# powersupply.net
KiCad netlist of a schematic drawn in Altium Designer
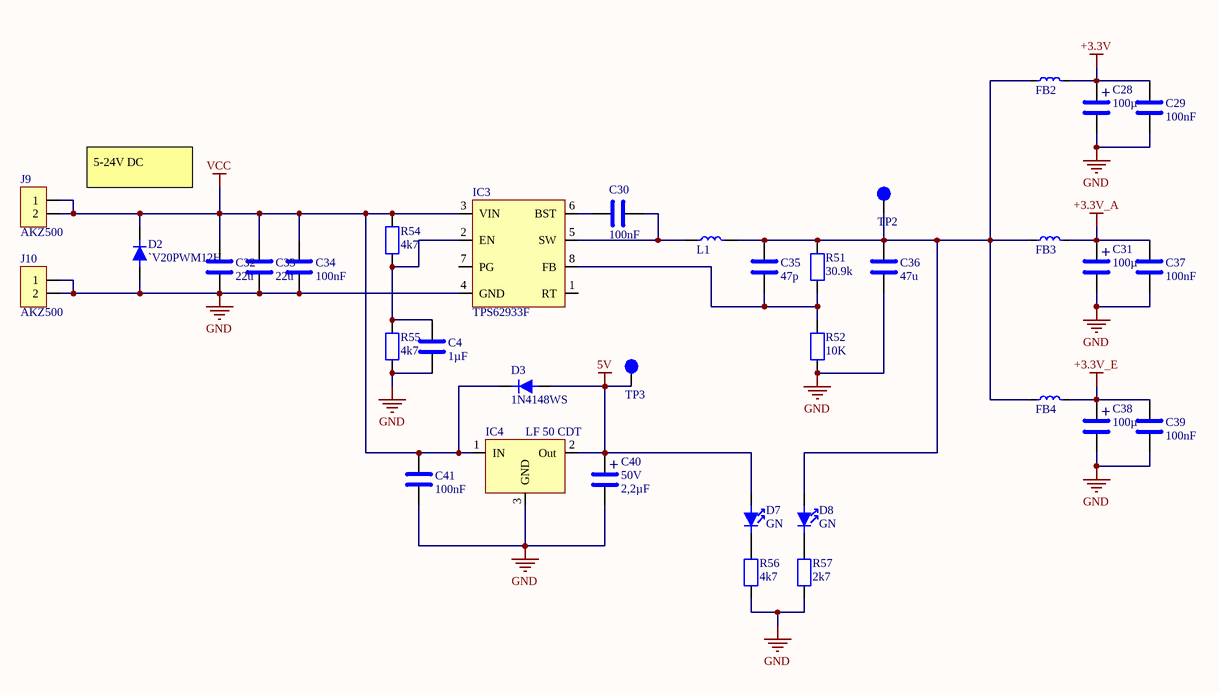
[diagram p0: powersupply.SchDoc]

(export (version "E")
  (design (tool "Eeschema 10.0.6"))
  (components
    (comp (ref "C4")
      (value "1µF")
      (footprint "0805")
      (description "1µF 25V MLCC 0805")
      (fields (field (name "VOLTAGE") "25V"))
      (libsource (lib "capacitor0805") (part "1µF 25V MLCC 0805"))
    )
    (comp (ref "C28")
      (value "100µ")
      (footprint "PANASONIC_C")
      (fields (field (name "VOLTAGE") "16V") (field (name "Comment") "Elko_100uF_16V_PanasonicC"))
      (libsource (lib "elkos") (part "Elko_100uF_16V_PanasonicC"))
    )
    (comp (ref "C29")
      (value "100nF")
      (footprint "0603")
      (description "100nF 50V MLCC 0603")
      (fields (field (name "VOLTAGE") "50V"))
      (libsource (lib "capacitors") (part "100nF 50V MLCC 0603"))
    )
    (comp (ref "C30")
      (value "100nF")
      (footprint "0603")
      (description "100nF 50V MLCC 0603")
      (fields (field (name "VOLTAGE") "50V"))
      (libsource (lib "capacitors") (part "100nF 50V MLCC 0603"))
    )
    (comp (ref "C31")
      (value "100µ")
      (footprint "PANASONIC_C")
      (fields (field (name "VOLTAGE") "16V") (field (name "Comment") "Elko_100uF_16V_PanasonicC"))
      (libsource (lib "elkos") (part "Elko_100uF_16V_PanasonicC"))
    )
    (comp (ref "C32")
      (value "22u")
      (footprint "1210")
      (description "22uF 35V X5R 1210")
      (fields (field (name "VOLTAGE") "35V"))
      (libsource (lib "capacitor1206") (part "22uF 35V X5R 1210"))
    )
    (comp (ref "C33")
      (value "22u")
      (footprint "1210")
      (description "22uF 35V X5R 1210")
      (fields (field (name "VOLTAGE") "35V"))
      (libsource (lib "capacitor1206") (part "22uF 35V X5R 1210"))
    )
    (comp (ref "C34")
      (value "100nF")
      (footprint "0603")
      (description "100nF 50V MLCC 0603")
      (fields (field (name "VOLTAGE") "50V"))
      (libsource (lib "capacitors") (part "100nF 50V MLCC 0603"))
    )
    (comp (ref "C35")
      (value "47p")
      (footprint "0603")
      (description "680pF 50V MLCC 0603")
      (fields (field (name "Comment") "47pF MLCC 0603"))
      (libsource (lib "capacitor0603") (part "47pF MLCC 0603"))
    )
    (comp (ref "C36")
      (value "47u")
      (footprint "1210")
      (description "47uF 16V X7R 1210")
      (fields (field (name "MOUSER PART") "GRM32ER61C476KE15L") (field (name "VOLTAGE") "16V"))
      (libsource (lib "capacitor1206") (part "47uF 16V X7R 1210"))
    )
    (comp (ref "C37")
      (value "100nF")
      (footprint "0603")
      (description "100nF 50V MLCC 0603")
      (fields (field (name "VOLTAGE") "50V"))
      (libsource (lib "capacitors") (part "100nF 50V MLCC 0603"))
    )
    (comp (ref "C38")
      (value "100µ")
      (footprint "PANASONIC_C")
      (fields (field (name "VOLTAGE") "16V") (field (name "Comment") "Elko_100uF_16V_PanasonicC"))
      (libsource (lib "elkos") (part "Elko_100uF_16V_PanasonicC"))
    )
    (comp (ref "C39")
      (value "100nF")
      (footprint "0603")
      (description "100nF 50V MLCC 0603")
      (fields (field (name "VOLTAGE") "50V"))
      (libsource (lib "capacitors") (part "100nF 50V MLCC 0603"))
    )
    (comp (ref "C40")
      (value "2,2µF 50V Size B Elko")
      (footprint "SIZE_B")
      (fields (field (name "VOLTAGE") "50V") (field (name "CAPACITANCE") "2,2µF"))
      (libsource (lib "elkos") (part "2,2µF 50V Size B Elko"))
    )
    (comp (ref "C41")
      (value "100nF")
      (footprint "0603")
      (description "100nF 50V MLCC 0603")
      (fields (field (name "VOLTAGE") "50V"))
      (libsource (lib "capacitors") (part "100nF 50V MLCC 0603"))
    )
    (comp (ref "D2")
      (value "`V20PWM12H")
      (footprint "TO-252AE")
      (description "20A high power diode")
      (libsource (lib "diodes") (part "V20PWM12HM3"))
    )
    (comp (ref "D3")
      (value "1N4148WS")
      (footprint "SOD323")
      (description "Small signal diode")
      (libsource (lib "diodes") (part "1N4148WS"))
    )
    (comp (ref "D7") (value "GN") (footprint "G0805") (libsource (lib "optos") (part "G0805 LED GN")))
    (comp (ref "D8") (value "GN") (footprint "G0805") (libsource (lib "optos") (part "G0805 LED GN")))
    (comp (ref "FB2")
      (value "HI1206N101R-10")
      (footprint "1206")
      (description "3A ferrit bead")
      (libsource (lib "inductors") (part "HI1206N101R-10"))
    )
    (comp (ref "FB3")
      (value "HI1206N101R-10")
      (footprint "1206")
      (description "3A ferrit bead")
      (libsource (lib "inductors") (part "HI1206N101R-10"))
    )
    (comp (ref "FB4")
      (value "HI1206N101R-10")
      (footprint "1206")
      (description "3A ferrit bead")
      (libsource (lib "inductors") (part "HI1206N101R-10"))
    )
    (comp (ref "IC3")
      (value "TPS62933F")
      (footprint "SOT583-8")
      (libsource (lib "regulators") (part "TPS62933F"))
    )
    (comp (ref "IC4")
      (value "LF 50 CDT")
      (footprint "D-PAK")
      (description "5V Spannungsregler D-PAK")
      (libsource (lib "regulators") (part "LF50CDT"))
    )
    (comp (ref "J9")
      (value "AKZ500")
      (footprint "AKZ500/2")
      (libsource (lib "connectors_screw") (part "AKZ500/2"))
    )
    (comp (ref "J10")
      (value "AKZ500")
      (footprint "AKZ500/2")
      (libsource (lib "connectors_screw") (part "AKZ500/2"))
    )
    (comp (ref "L1")
      (value "SRN5040-8R2M")
      (footprint "BOURNS SRN5040")
      (libsource (lib "inductors") (part "SRN5040-8R2M"))
    )
    (comp (ref "R51")
      (value "30.9k")
      (footprint "res0603")
      (description "30k9 100mW 0603")
      (fields (field (name "TOLERANCE") "1%"))
      (libsource (lib "resistors0603") (part "30k9 100mW 0603"))
    )
    (comp (ref "R52")
      (value "10K")
      (footprint "res0603")
      (description "10K 100mW 0603")
      (fields (field (name "TOLERANCE") "1%"))
      (libsource (lib "resistors") (part "10K 100mW 0603"))
    )
    (comp (ref "R54")
      (value "4k7")
      (footprint "res0603")
      (description "4k7 100mW 0603")
      (libsource (lib "resistors") (part "4k7 100mW 0603"))
    )
    (comp (ref "R55")
      (value "4k7")
      (footprint "res0603")
      (description "4k7 100mW 0603")
      (libsource (lib "resistors") (part "4k7 100mW 0603"))
    )
    (comp (ref "R56")
      (value "4k7")
      (footprint "res0603")
      (description "4k7 100mW 0603")
      (libsource (lib "resistors") (part "4k7 100mW 0603"))
    )
    (comp (ref "R57")
      (value "2k7")
      (footprint "res0603")
      (description "2k7 100mW 0603")
      (fields (field (name "TOLERANCE") "1%"))
      (libsource (lib "resistors") (part "2k7 100mW 0603"))
    )
    (comp (ref "TP2") (value "testpoint") (footprint "testpoint") (libsource (lib "misc") (part "testpoint")))
    (comp (ref "TP3") (value "testpoint") (footprint "testpoint") (libsource (lib "misc") (part "testpoint")))
  )
  (nets
    (net (code "1") (name "+3.3V") (class "Default")
      (node (ref "C28") (pin "+") (pinfunction "+_+") (pintype "passive"))
      (node (ref "C29") (pin "1") (pinfunction "1_1") (pintype "passive"))
      (node (ref "FB2") (pin "2") (pinfunction "2_2") (pintype "passive"))
    )
    (net (code "2") (name "+3.3V_A") (class "Default")
      (node (ref "C31") (pin "+") (pinfunction "+_+") (pintype "passive"))
      (node (ref "C37") (pin "1") (pinfunction "1_1") (pintype "passive"))
      (node (ref "FB3") (pin "2") (pinfunction "2_2") (pintype "passive"))
    )
    (net (code "3") (name "+3.3V_E") (class "Default")
      (node (ref "C38") (pin "+") (pinfunction "+_+") (pintype "passive"))
      (node (ref "C39") (pin "1") (pinfunction "1_1") (pintype "passive"))
      (node (ref "FB4") (pin "2") (pinfunction "2_2") (pintype "passive"))
    )
    (net (code "4") (name "5V") (class "Default")
      (node (ref "C40") (pin "1") (pinfunction "1_1") (pintype "passive"))
      (node (ref "D3") (pin "2") (pinfunction "2_2") (pintype "passive"))
      (node (ref "D7") (pin "2") (pinfunction "2_2") (pintype "passive"))
      (node (ref "IC4") (pin "2") (pinfunction "Out_2") (pintype "passive"))
      (node (ref "TP3") (pin "1") (pinfunction "1_1") (pintype "passive"))
    )
    (net (code "5") (name "GND") (class "Default")
      (node (ref "C28") (pin "-") (pinfunction "-_-") (pintype "passive"))
      (node (ref "C29") (pin "2") (pinfunction "2_2") (pintype "passive"))
      (node (ref "C31") (pin "-") (pinfunction "-_-") (pintype "passive"))
      (node (ref "C32") (pin "2") (pinfunction "2_2") (pintype "passive"))
      (node (ref "C33") (pin "2") (pinfunction "2_2") (pintype "passive"))
      (node (ref "C34") (pin "2") (pinfunction "2_2") (pintype "passive"))
      (node (ref "C36") (pin "2") (pinfunction "2_2") (pintype "passive"))
      (node (ref "C37") (pin "2") (pinfunction "2_2") (pintype "passive"))
      (node (ref "C38") (pin "-") (pinfunction "-_-") (pintype "passive"))
      (node (ref "C39") (pin "2") (pinfunction "2_2") (pintype "passive"))
      (node (ref "C4") (pin "2") (pinfunction "2_2") (pintype "passive"))
      (node (ref "C40") (pin "2") (pinfunction "2_2") (pintype "passive"))
      (node (ref "C41") (pin "1") (pinfunction "1_1") (pintype "passive"))
      (node (ref "D2") (pin "2") (pinfunction "2_2") (pintype "passive"))
      (node (ref "IC3") (pin "4") (pinfunction "GND_4") (pintype "passive"))
      (node (ref "IC4") (pin "3") (pinfunction "GND_3") (pintype "passive"))
      (node (ref "J10") (pin "1") (pinfunction "1_1") (pintype "passive"))
      (node (ref "J10") (pin "2") (pinfunction "2_2") (pintype "passive"))
      (node (ref "R52") (pin "1") (pinfunction "1_1") (pintype "passive"))
      (node (ref "R55") (pin "1") (pinfunction "1_1") (pintype "passive"))
      (node (ref "R56") (pin "1") (pinfunction "1_1") (pintype "passive"))
      (node (ref "R57") (pin "1") (pinfunction "1_1") (pintype "passive"))
    )
    (net (code "6") (name "Net-(C35-Pad1)") (class "Default")
      (node (ref "C35") (pin "1") (pinfunction "1_1") (pintype "passive"))
      (node (ref "C36") (pin "1") (pinfunction "1_1") (pintype "passive"))
      (node (ref "D8") (pin "2") (pinfunction "2_2") (pintype "passive"))
      (node (ref "FB2") (pin "1") (pinfunction "1_1") (pintype "passive"))
      (node (ref "FB3") (pin "1") (pinfunction "1_1") (pintype "passive"))
      (node (ref "FB4") (pin "1") (pinfunction "1_1") (pintype "passive"))
      (node (ref "L1") (pin "2") (pinfunction "2_2") (pintype "passive"))
      (node (ref "R51") (pin "2") (pinfunction "2_2") (pintype "passive"))
      (node (ref "TP2") (pin "1") (pinfunction "1_1") (pintype "passive"))
    )
    (net (code "7") (name "Net-(D7-Pad1)") (class "Default")
      (node (ref "D7") (pin "1") (pinfunction "1_1") (pintype "passive"))
      (node (ref "R56") (pin "2") (pinfunction "2_2") (pintype "passive"))
    )
    (net (code "8") (name "Net-(D8-Pad1)") (class "Default")
      (node (ref "D8") (pin "1") (pinfunction "1_1") (pintype "passive"))
      (node (ref "R57") (pin "2") (pinfunction "2_2") (pintype "passive"))
    )
    (net (code "9") (name "Net-(IC3-BST)") (class "Default")
      (node (ref "C30") (pin "1") (pinfunction "1_1") (pintype "passive"))
      (node (ref "IC3") (pin "6") (pinfunction "BST_6") (pintype "passive"))
    )
    (net (code "10") (name "Net-(IC3-EN)") (class "Default")
      (node (ref "C4") (pin "1") (pinfunction "1_1") (pintype "passive"))
      (node (ref "IC3") (pin "2") (pinfunction "EN_2") (pintype "passive"))
      (node (ref "R54") (pin "1") (pinfunction "1_1") (pintype "passive"))
      (node (ref "R55") (pin "2") (pinfunction "2_2") (pintype "passive"))
    )
    (net (code "11") (name "Net-(IC3-FB)") (class "Default")
      (node (ref "C35") (pin "2") (pinfunction "2_2") (pintype "passive"))
      (node (ref "IC3") (pin "8") (pinfunction "FB_8") (pintype "passive"))
      (node (ref "R51") (pin "1") (pinfunction "1_1") (pintype "passive"))
      (node (ref "R52") (pin "2") (pinfunction "2_2") (pintype "passive"))
    )
    (net (code "12") (name "Net-(IC3-SW)") (class "Default")
      (node (ref "C30") (pin "2") (pinfunction "2_2") (pintype "passive"))
      (node (ref "IC3") (pin "5") (pinfunction "SW_5") (pintype "passive"))
      (node (ref "L1") (pin "1") (pinfunction "1_1") (pintype "passive"))
    )
    (net (code "13") (name "VCC") (class "Default")
      (node (ref "C32") (pin "1") (pinfunction "1_1") (pintype "passive"))
      (node (ref "C33") (pin "1") (pinfunction "1_1") (pintype "passive"))
      (node (ref "C34") (pin "1") (pinfunction "1_1") (pintype "passive"))
      (node (ref "C41") (pin "2") (pinfunction "2_2") (pintype "passive"))
      (node (ref "D2") (pin "1") (pinfunction "1_1") (pintype "passive"))
      (node (ref "D3") (pin "1") (pinfunction "1_1") (pintype "passive"))
      (node (ref "IC3") (pin "3") (pinfunction "VIN_3") (pintype "passive"))
      (node (ref "IC4") (pin "1") (pinfunction "IN_1") (pintype "passive"))
      (node (ref "J9") (pin "1") (pinfunction "1_1") (pintype "passive"))
      (node (ref "J9") (pin "2") (pinfunction "2_2") (pintype "passive"))
      (node (ref "R54") (pin "2") (pinfunction "2_2") (pintype "passive"))
    )
    (net (code "14") (name "unconnected-(IC3-PG-Pad7)") (class "Default")
      (node (ref "IC3") (pin "7") (pinfunction "PG_7") (pintype "passive"))
    )
    (net (code "15") (name "unconnected-(IC3-RT-Pad1)") (class "Default")
      (node (ref "IC3") (pin "1") (pinfunction "RT_1") (pintype "passive"))
    )
  )
)
